# ti_can.net
KiCad netlist of a schematic drawn in EAGLE
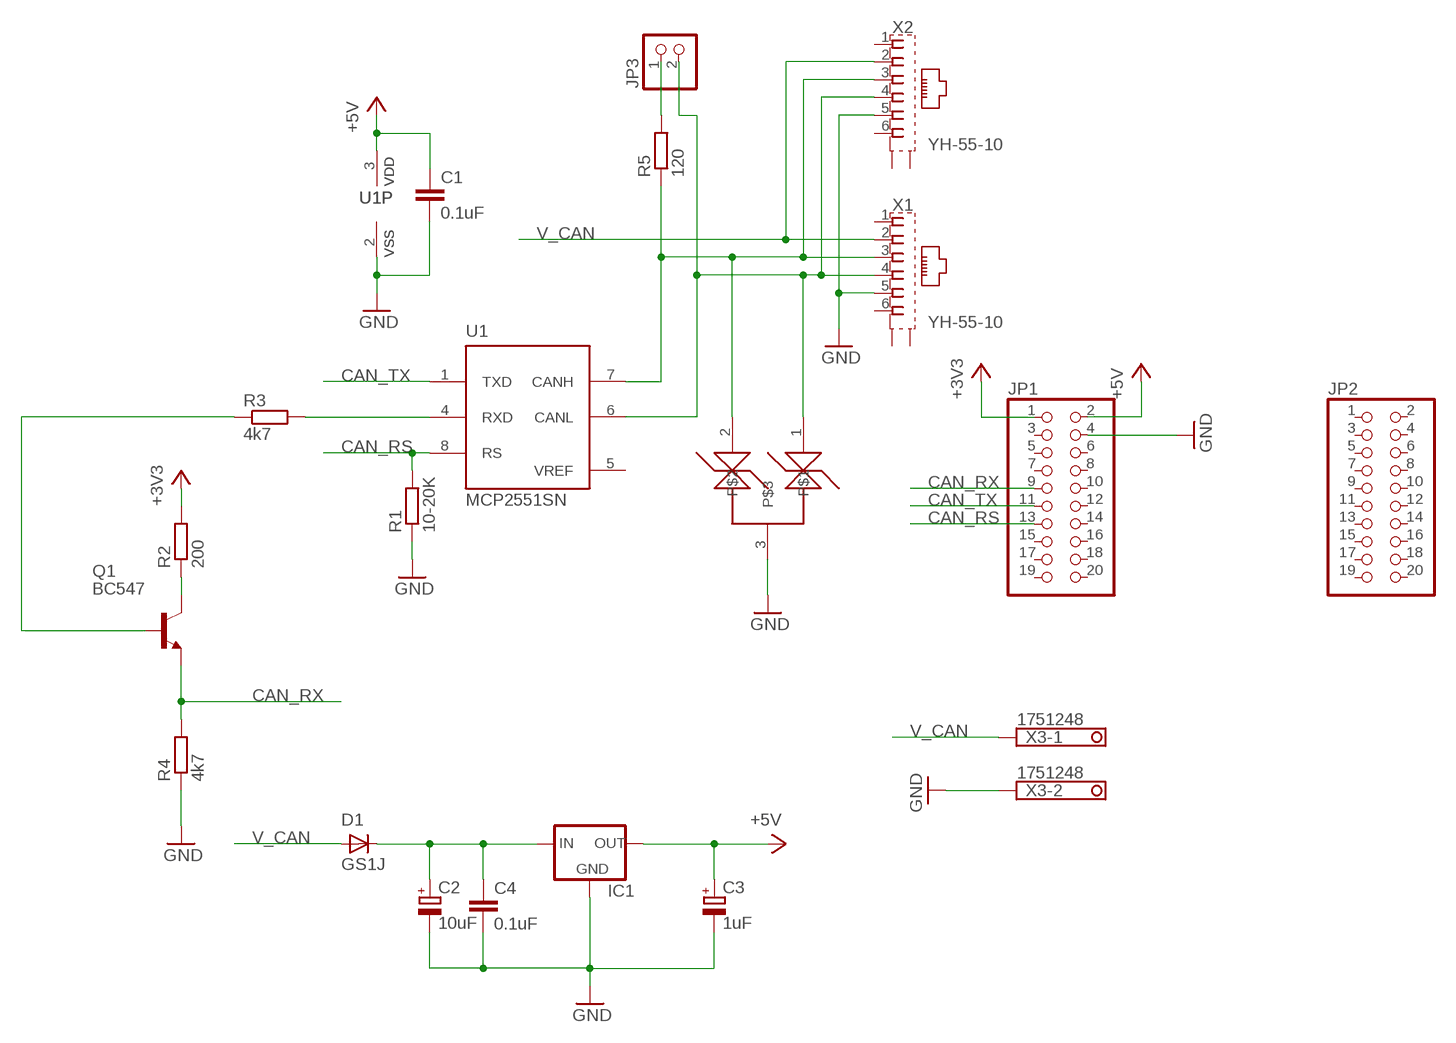
[diagram p0: schematic, sheet 1]

(export (version "E")
  (design (tool "Eeschema 10.0.6"))
  (components
    (comp (ref "C1")
      (value "0.1uF")
      (footprint "eagle-import:C0805")
      (libsource (lib "eagle-import") (part "C-EUC0805"))
    )
    (comp (ref "C2")
      (value "10uF")
      (footprint "eagle-import:E2,5-6E")
      (libsource (lib "eagle-import") (part "CPOL-EUE2,5-6E"))
    )
    (comp (ref "C3")
      (value "1uF")
      (footprint "eagle-import:E2,5-6E")
      (libsource (lib "eagle-import") (part "CPOL-EUE2,5-6E"))
    )
    (comp (ref "C4")
      (value "0.1uF")
      (footprint "eagle-import:C0805")
      (libsource (lib "eagle-import") (part "C-EUC0805"))
    )
    (comp (ref "D1")
      (value "GS1J")
      (footprint "eagle-import:SMA-DO214AC")
      (libsource (lib "eagle-import") (part "GF1"))
    )
    (comp (ref "IC1")
      (value "LP2950CDT-5.0")
      (footprint "eagle-import:DPACK")
      (libsource (lib "eagle-import") (part "LP2950?CDT-5.0"))
    )
    (comp (ref "JP1")
      (value "PINHD-2X10")
      (footprint "eagle-import:2X10")
      (libsource (lib "eagle-import") (part "PINHD-2X10"))
    )
    (comp (ref "JP2")
      (value "PINHD-2X10")
      (footprint "eagle-import:2X10")
      (libsource (lib "eagle-import") (part "PINHD-2X10"))
    )
    (comp (ref "JP3")
      (value "PINHD-1X2")
      (footprint "eagle-import:1X02")
      (libsource (lib "eagle-import") (part "PINHD-1X2"))
    )
    (comp (ref "Q1")
      (value "BC547")
      (footprint "eagle-import:TO92")
      (libsource (lib "eagle-import") (part "BC547"))
    )
    (comp (ref "R1")
      (value "10-20K")
      (footprint "eagle-import:M0805")
      (libsource (lib "eagle-import") (part "R-EU_M0805"))
    )
    (comp (ref "R2")
      (value "200")
      (footprint "eagle-import:M0805")
      (libsource (lib "eagle-import") (part "R-EU_M0805"))
    )
    (comp (ref "R3")
      (value "4k7")
      (footprint "eagle-import:M0805")
      (libsource (lib "eagle-import") (part "R-EU_M0805"))
    )
    (comp (ref "R4")
      (value "4k7")
      (footprint "eagle-import:M0805")
      (libsource (lib "eagle-import") (part "R-EU_M0805"))
    )
    (comp (ref "R5")
      (value "120")
      (footprint "eagle-import:0207_2V")
      (libsource (lib "eagle-import") (part "R-EU_0207/2V"))
    )
    (comp (ref "U$1")
      (value "NUP2105L")
      (footprint "eagle-import:SOT23")
      (libsource (lib "eagle-import") (part "NUP2105L"))
    )
    (comp (ref "U1")
      (value "MCP2551SN")
      (footprint "eagle-import:SO-08")
      (libsource (lib "eagle-import") (part "MCP2551SN"))
    )
    (comp (ref "X1")
      (value "YH-55-10")
      (footprint "eagle-import:YH-55-10")
      (libsource (lib "eagle-import") (part "YH-55-10"))
    )
    (comp (ref "X2")
      (value "YH-55-10")
      (footprint "eagle-import:YH-55-10")
      (fields (field (name "OC_FARNELL") "unknown") (field (name "OC_NEWARK") "unknown"))
      (libsource (lib "eagle-import") (part "YH-55-10"))
    )
    (comp (ref "X3")
      (value "1751248")
      (footprint "eagle-import:1751248")
      (libsource (lib "eagle-import") (part "1751248"))
    )
  )
  (nets
    (net (code "1") (name "+3V3") (class "Default")
      (node (ref "JP1") (pin "1") (pinfunction "1_1") (pintype "passive"))
      (node (ref "R2") (pin "2") (pinfunction "2_2") (pintype "passive"))
    )
    (net (code "2") (name "+5V") (class "Default")
      (node (ref "C1") (pin "1") (pinfunction "1_1") (pintype "passive"))
      (node (ref "C3") (pin "+") (pinfunction "+_+") (pintype "passive"))
      (node (ref "IC1") (pin "3") (pinfunction "OUT_3") (pintype "passive"))
      (node (ref "JP1") (pin "2") (pinfunction "2_2") (pintype "passive"))
      (node (ref "U1") (pin "3") (pinfunction "VDD_3") (pintype "power_in"))
    )
    (net (code "3") (name "/CAN_RS") (class "Default")
      (node (ref "JP1") (pin "13") (pinfunction "13_13") (pintype "passive"))
      (node (ref "R1") (pin "2") (pinfunction "2_2") (pintype "passive"))
      (node (ref "U1") (pin "8") (pinfunction "RS_8") (pintype "input"))
    )
    (net (code "4") (name "/CAN_RX") (class "Default")
      (node (ref "JP1") (pin "9") (pinfunction "9_9") (pintype "passive"))
      (node (ref "Q1") (pin "1") (pinfunction "E_1") (pintype "passive"))
      (node (ref "R4") (pin "2") (pinfunction "2_2") (pintype "passive"))
    )
    (net (code "5") (name "/CAN_TX") (class "Default")
      (node (ref "JP1") (pin "11") (pinfunction "11_11") (pintype "passive"))
      (node (ref "U1") (pin "1") (pinfunction "TXD_1") (pintype "input"))
    )
    (net (code "6") (name "/VREF") (class "Default")
      (node (ref "U1") (pin "5") (pinfunction "VREF_5") (pintype "power_in"))
    )
    (net (code "7") (name "/V_CAN") (class "Default")
      (node (ref "D1") (pin "A") (pinfunction "A_A") (pintype "passive"))
      (node (ref "X1") (pin "2") (pinfunction "2_2") (pintype "passive"))
      (node (ref "X2") (pin "2") (pinfunction "2_2") (pintype "passive"))
      (node (ref "X3") (pin "1") (pinfunction "K_1") (pintype "passive"))
    )
    (net (code "8") (name "GND") (class "Default")
      (node (ref "C1") (pin "2") (pinfunction "2_2") (pintype "passive"))
      (node (ref "C2") (pin "-") (pinfunction "-_-") (pintype "passive"))
      (node (ref "C3") (pin "-") (pinfunction "-_-") (pintype "passive"))
      (node (ref "C4") (pin "2") (pinfunction "2_2") (pintype "passive"))
      (node (ref "IC1") (pin "4") (pinfunction "GND_4") (pintype "input"))
      (node (ref "JP1") (pin "4") (pinfunction "4_4") (pintype "passive"))
      (node (ref "R1") (pin "1") (pinfunction "1_1") (pintype "passive"))
      (node (ref "R4") (pin "1") (pinfunction "1_1") (pintype "passive"))
      (node (ref "U$1") (pin "3") (pinfunction "P$3_3") (pintype "bidirectional"))
      (node (ref "U1") (pin "2") (pinfunction "VSS_2") (pintype "power_in"))
      (node (ref "X1") (pin "5") (pinfunction "5_5") (pintype "passive"))
      (node (ref "X2") (pin "5") (pinfunction "5_5") (pintype "passive"))
      (node (ref "X3") (pin "2") (pinfunction "K_2") (pintype "passive"))
    )
    (net (code "9") (name "Net-(D1-C)") (class "Default")
      (node (ref "C2") (pin "+") (pinfunction "+_+") (pintype "passive"))
      (node (ref "C4") (pin "1") (pinfunction "1_1") (pintype "passive"))
      (node (ref "D1") (pin "K") (pinfunction "C_K") (pintype "passive"))
      (node (ref "IC1") (pin "1") (pinfunction "IN_1") (pintype "input"))
    )
    (net (code "10") (name "Net-(JP3-Pad1)") (class "Default")
      (node (ref "JP3") (pin "1") (pinfunction "1_1") (pintype "passive"))
      (node (ref "R5") (pin "2") (pinfunction "2_2") (pintype "passive"))
    )
    (net (code "11") (name "Net-(Q1-B)") (class "Default")
      (node (ref "Q1") (pin "2") (pinfunction "B_2") (pintype "passive"))
      (node (ref "R3") (pin "1") (pinfunction "1_1") (pintype "passive"))
    )
    (net (code "12") (name "Net-(Q1-C)") (class "Default")
      (node (ref "Q1") (pin "3") (pinfunction "C_3") (pintype "passive"))
      (node (ref "R2") (pin "1") (pinfunction "1_1") (pintype "passive"))
    )
    (net (code "13") (name "Net-(U$1-P$1)") (class "Default")
      (node (ref "JP3") (pin "2") (pinfunction "2_2") (pintype "passive"))
      (node (ref "U$1") (pin "1") (pinfunction "P$1_1") (pintype "bidirectional"))
      (node (ref "U1") (pin "6") (pinfunction "CANL_6") (pintype "bidirectional"))
      (node (ref "X1") (pin "4") (pinfunction "4_4") (pintype "passive"))
      (node (ref "X2") (pin "4") (pinfunction "4_4") (pintype "passive"))
    )
    (net (code "14") (name "Net-(U$1-P$2)") (class "Default")
      (node (ref "R5") (pin "1") (pinfunction "1_1") (pintype "passive"))
      (node (ref "U$1") (pin "2") (pinfunction "P$2_2") (pintype "bidirectional"))
      (node (ref "U1") (pin "7") (pinfunction "CANH_7") (pintype "bidirectional"))
      (node (ref "X1") (pin "3") (pinfunction "3_3") (pintype "passive"))
      (node (ref "X2") (pin "3") (pinfunction "3_3") (pintype "passive"))
    )
    (net (code "15") (name "Net-(U1A-RXD)") (class "Default")
      (node (ref "R3") (pin "2") (pinfunction "2_2") (pintype "passive"))
      (node (ref "U1") (pin "4") (pinfunction "RXD_4") (pintype "output"))
    )
    (net (code "16") (name "unconnected-(JP1-Pad3)") (class "Default")
      (node (ref "JP1") (pin "3") (pinfunction "3_3") (pintype "passive"))
    )
    (net (code "17") (name "unconnected-(JP1-Pad5)") (class "Default")
      (node (ref "JP1") (pin "5") (pinfunction "5_5") (pintype "passive"))
    )
    (net (code "18") (name "unconnected-(JP1-Pad6)") (class "Default")
      (node (ref "JP1") (pin "6") (pinfunction "6_6") (pintype "passive"))
    )
    (net (code "19") (name "unconnected-(JP1-Pad7)") (class "Default")
      (node (ref "JP1") (pin "7") (pinfunction "7_7") (pintype "passive"))
    )
    (net (code "20") (name "unconnected-(JP1-Pad8)") (class "Default")
      (node (ref "JP1") (pin "8") (pinfunction "8_8") (pintype "passive"))
    )
    (net (code "21") (name "unconnected-(JP1-Pad10)") (class "Default")
      (node (ref "JP1") (pin "10") (pinfunction "10_10") (pintype "passive"))
    )
    (net (code "22") (name "unconnected-(JP1-Pad12)") (class "Default")
      (node (ref "JP1") (pin "12") (pinfunction "12_12") (pintype "passive"))
    )
    (net (code "23") (name "unconnected-(JP1-Pad14)") (class "Default")
      (node (ref "JP1") (pin "14") (pinfunction "14_14") (pintype "passive"))
    )
    (net (code "24") (name "unconnected-(JP1-Pad15)") (class "Default")
      (node (ref "JP1") (pin "15") (pinfunction "15_15") (pintype "passive"))
    )
    (net (code "25") (name "unconnected-(JP1-Pad16)") (class "Default")
      (node (ref "JP1") (pin "16") (pinfunction "16_16") (pintype "passive"))
    )
    (net (code "26") (name "unconnected-(JP1-Pad17)") (class "Default")
      (node (ref "JP1") (pin "17") (pinfunction "17_17") (pintype "passive"))
    )
    (net (code "27") (name "unconnected-(JP1-Pad18)") (class "Default")
      (node (ref "JP1") (pin "18") (pinfunction "18_18") (pintype "passive"))
    )
    (net (code "28") (name "unconnected-(JP1-Pad19)") (class "Default")
      (node (ref "JP1") (pin "19") (pinfunction "19_19") (pintype "passive"))
    )
    (net (code "29") (name "unconnected-(JP1-Pad20)") (class "Default")
      (node (ref "JP1") (pin "20") (pinfunction "20_20") (pintype "passive"))
    )
    (net (code "30") (name "unconnected-(JP2-Pad1)") (class "Default")
      (node (ref "JP2") (pin "1") (pinfunction "1_1") (pintype "passive"))
    )
    (net (code "31") (name "unconnected-(JP2-Pad2)") (class "Default")
      (node (ref "JP2") (pin "2") (pinfunction "2_2") (pintype "passive"))
    )
    (net (code "32") (name "unconnected-(JP2-Pad3)") (class "Default")
      (node (ref "JP2") (pin "3") (pinfunction "3_3") (pintype "passive"))
    )
    (net (code "33") (name "unconnected-(JP2-Pad4)") (class "Default")
      (node (ref "JP2") (pin "4") (pinfunction "4_4") (pintype "passive"))
    )
    (net (code "34") (name "unconnected-(JP2-Pad5)") (class "Default")
      (node (ref "JP2") (pin "5") (pinfunction "5_5") (pintype "passive"))
    )
    (net (code "35") (name "unconnected-(JP2-Pad6)") (class "Default")
      (node (ref "JP2") (pin "6") (pinfunction "6_6") (pintype "passive"))
    )
    (net (code "36") (name "unconnected-(JP2-Pad7)") (class "Default")
      (node (ref "JP2") (pin "7") (pinfunction "7_7") (pintype "passive"))
    )
    (net (code "37") (name "unconnected-(JP2-Pad8)") (class "Default")
      (node (ref "JP2") (pin "8") (pinfunction "8_8") (pintype "passive"))
    )
    (net (code "38") (name "unconnected-(JP2-Pad9)") (class "Default")
      (node (ref "JP2") (pin "9") (pinfunction "9_9") (pintype "passive"))
    )
    (net (code "39") (name "unconnected-(JP2-Pad10)") (class "Default")
      (node (ref "JP2") (pin "10") (pinfunction "10_10") (pintype "passive"))
    )
    (net (code "40") (name "unconnected-(JP2-Pad11)") (class "Default")
      (node (ref "JP2") (pin "11") (pinfunction "11_11") (pintype "passive"))
    )
    (net (code "41") (name "unconnected-(JP2-Pad12)") (class "Default")
      (node (ref "JP2") (pin "12") (pinfunction "12_12") (pintype "passive"))
    )
    (net (code "42") (name "unconnected-(JP2-Pad13)") (class "Default")
      (node (ref "JP2") (pin "13") (pinfunction "13_13") (pintype "passive"))
    )
    (net (code "43") (name "unconnected-(JP2-Pad14)") (class "Default")
      (node (ref "JP2") (pin "14") (pinfunction "14_14") (pintype "passive"))
    )
    (net (code "44") (name "unconnected-(JP2-Pad15)") (class "Default")
      (node (ref "JP2") (pin "15") (pinfunction "15_15") (pintype "passive"))
    )
    (net (code "45") (name "unconnected-(JP2-Pad16)") (class "Default")
      (node (ref "JP2") (pin "16") (pinfunction "16_16") (pintype "passive"))
    )
    (net (code "46") (name "unconnected-(JP2-Pad17)") (class "Default")
      (node (ref "JP2") (pin "17") (pinfunction "17_17") (pintype "passive"))
    )
    (net (code "47") (name "unconnected-(JP2-Pad18)") (class "Default")
      (node (ref "JP2") (pin "18") (pinfunction "18_18") (pintype "passive"))
    )
    (net (code "48") (name "unconnected-(JP2-Pad19)") (class "Default")
      (node (ref "JP2") (pin "19") (pinfunction "19_19") (pintype "passive"))
    )
    (net (code "49") (name "unconnected-(JP2-Pad20)") (class "Default")
      (node (ref "JP2") (pin "20") (pinfunction "20_20") (pintype "passive"))
    )
    (net (code "50") (name "unconnected-(X1-Pad1)") (class "Default")
      (node (ref "X1") (pin "1") (pinfunction "1_1") (pintype "passive"))
    )
    (net (code "51") (name "unconnected-(X1-Pad6)") (class "Default")
      (node (ref "X1") (pin "6") (pinfunction "6_6") (pintype "passive"))
    )
    (net (code "52") (name "unconnected-(X1-S-PadS1)") (class "Default")
      (node (ref "X1") (pin "S1") (pinfunction "S_S1") (pintype "passive"))
    )
    (net (code "53") (name "unconnected-(X1-S-PadS2)") (class "Default")
      (node (ref "X1") (pin "S2") (pinfunction "S_S2") (pintype "passive"))
    )
    (net (code "54") (name "unconnected-(X2-Pad1)") (class "Default")
      (node (ref "X2") (pin "1") (pinfunction "1_1") (pintype "passive"))
    )
    (net (code "55") (name "unconnected-(X2-Pad6)") (class "Default")
      (node (ref "X2") (pin "6") (pinfunction "6_6") (pintype "passive"))
    )
    (net (code "56") (name "unconnected-(X2-S-PadS1)") (class "Default")
      (node (ref "X2") (pin "S1") (pinfunction "S_S1") (pintype "passive"))
    )
    (net (code "57") (name "unconnected-(X2-S-PadS2)") (class "Default")
      (node (ref "X2") (pin "S2") (pinfunction "S_S2") (pintype "passive"))
    )
  )
)
